# MCISO-S05-V00-CANIsolation.net
KiCad netlist of a schematic drawn in Altium Designer
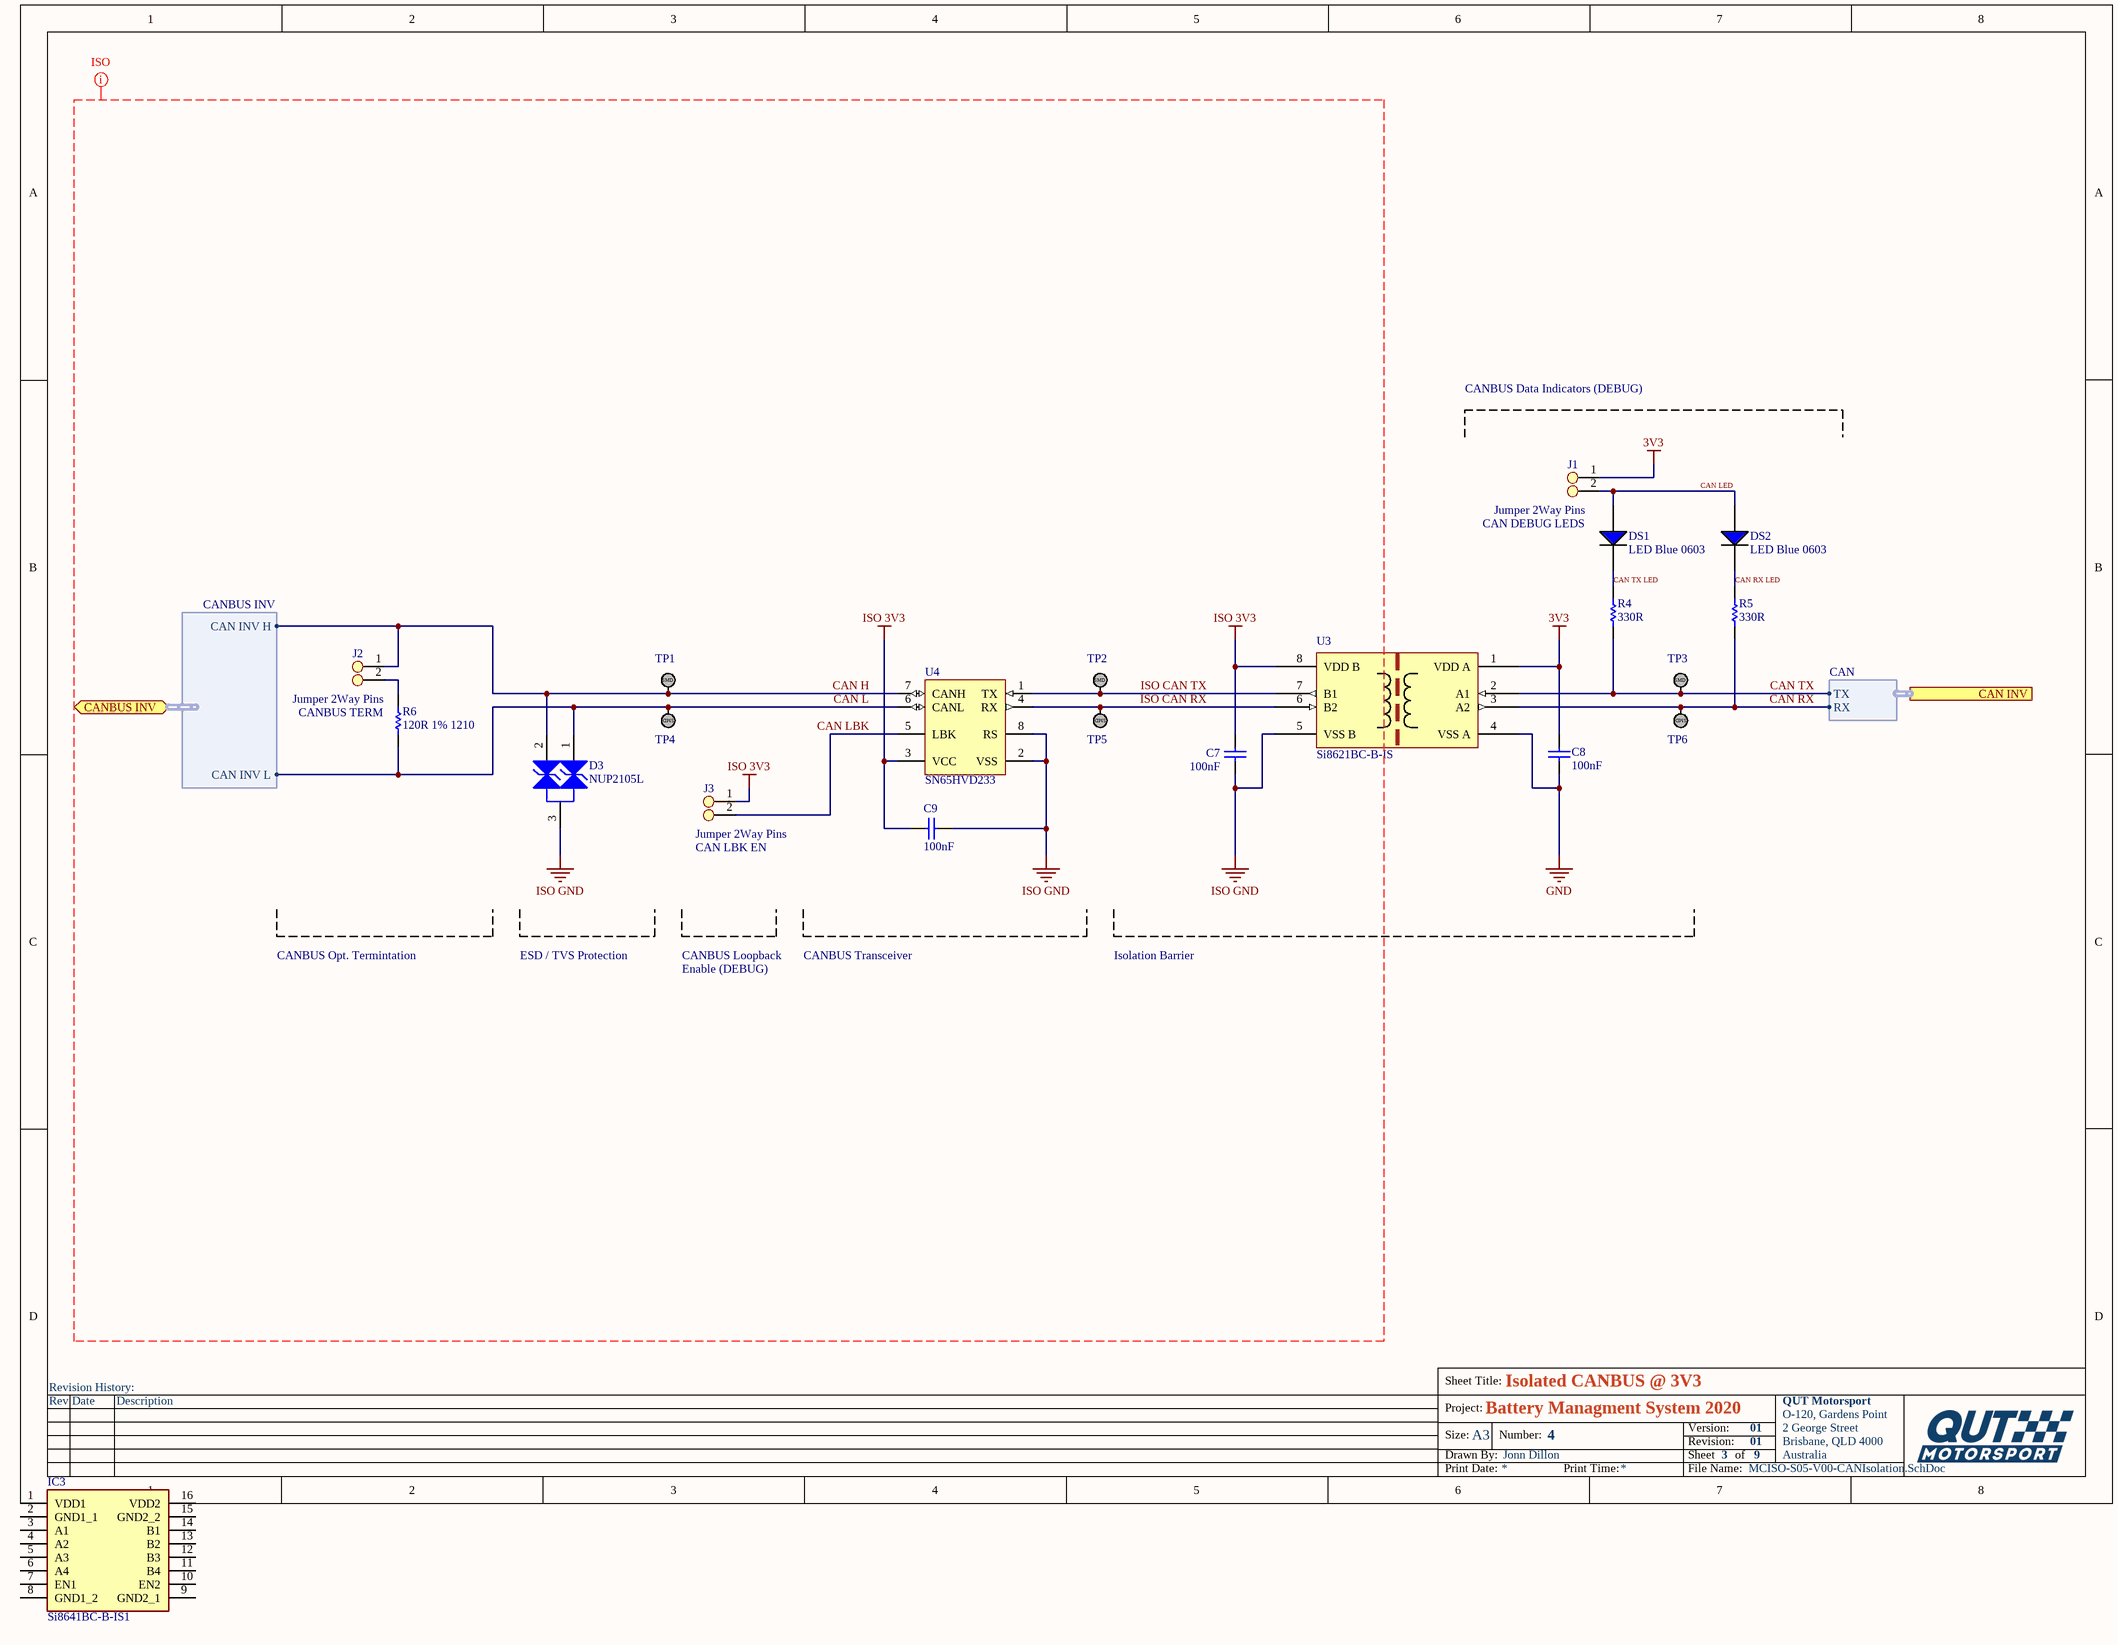
[diagram p0: MCISO-S05-V00-CANIsolation.SchDoc]

(export (version "E")
  (design (tool "Eeschema 10.0.6"))
  (components
    (comp (ref "C7")
      (value "100nF")
      (footprint "Cap_Ceramic_0603")
      (description "Capacitor, Ceramic, SMD, 100nF, 50V, 5%, X7R, 0603")
      (libsource (lib "StandardCapacitors") (part "100nF 50V 5% X7R 0603"))
    )
    (comp (ref "C8")
      (value "100nF")
      (footprint "Cap_Ceramic_0603")
      (description "Capacitor, Ceramic, SMD, 100nF, 50V, 5%, X7R, 0603")
      (libsource (lib "StandardCapacitors") (part "100nF 50V 5% X7R 0603"))
    )
    (comp (ref "C9")
      (value "100nF")
      (footprint "Cap_Ceramic_0603")
      (description "Capacitor, Ceramic, SMD, 100nF, 50V, 5%, X7R, 0603")
      (libsource (lib "StandardCapacitors") (part "100nF 50V 5% X7R 0603"))
    )
    (comp (ref "D3")
      (value "NUP2105L")
      (footprint "NUP2105L")
      (libsource (lib "QUTMS_CANLibrary") (part "NUP2105L"))
    )
    (comp (ref "DS1")
      (value "LED Blue 0603")
      (footprint "LED BLUE 0603")
      (libsource (lib "QUTMS_LEDLibrary") (part "LED BLUE 0603"))
    )
    (comp (ref "DS2")
      (value "LED Blue 0603")
      (footprint "LED BLUE 0603")
      (libsource (lib "QUTMS_LEDLibrary") (part "LED BLUE 0603"))
    )
    (comp (ref "IC3")
      (value "Si8641BC-B-IS1")
      (footprint "SamacSys:SOIC127P600X175-16N")
      (description "Integrated Circuit")
      (fields
        (field (name "MOUSER PART NUMBER") "634-SI8641BC-B-IS1")
        (field (name "ARROW PART NUMBER") "SI8641BC-B-IS1")
      )
      (libsource (lib "*") (part "Si8641BC-B-IS1"))
    )
    (comp (ref "J1")
      (value "Jumper 2Way Pins")
      (footprint "Jumper_2Way_Pin")
      (description "Jumper 2Way Side Pins")
      (libsource (lib "QUTMS_JumperLibrary") (part "Jumper 2Way Side Pins"))
    )
    (comp (ref "J2")
      (value "Jumper 2Way Pins")
      (footprint "Jumper_2Way_Pin")
      (description "Jumper 2Way Side Pins")
      (libsource (lib "QUTMS_JumperLibrary") (part "Jumper 2Way Side Pins"))
    )
    (comp (ref "J3")
      (value "Jumper 2Way Pins")
      (footprint "Jumper_2Way_Pin")
      (description "Jumper 2Way Side Pins")
      (libsource (lib "QUTMS_JumperLibrary") (part "Jumper 2Way Side Pins"))
    )
    (comp (ref "R4")
      (value "330R")
      (footprint "Res_ThinFilm_0603")
      (description "Resistor, SMD, 330R, 0.1W, 5%, 0603")
      (libsource (lib "StandardResistors") (part "330R 5% 0603"))
    )
    (comp (ref "R5")
      (value "330R")
      (footprint "Res_ThinFilm_0603")
      (description "Resistor, SMD, 330R, 0.1W, 5%, 0603")
      (libsource (lib "StandardResistors") (part "330R 5% 0603"))
    )
    (comp (ref "R6")
      (value "120R 1% 1210")
      (footprint "Res_ThinFilm_1210")
      (description "Resistor, SMD, 120R, 0.25W, 1%, 1210")
      (libsource (lib "StandardResistors") (part "120R 1% 1210"))
    )
    (comp (ref "TP1")
      (value "TestPoint_SMD")
      (footprint "TestPointSMD")
      (libsource (lib "StandardTest") (part "TestPoint_SMD"))
    )
    (comp (ref "TP2")
      (value "TestPoint_SMD")
      (footprint "TestPointSMD")
      (libsource (lib "StandardTest") (part "TestPoint_SMD"))
    )
    (comp (ref "TP3")
      (value "TestPoint_SMD")
      (footprint "TestPointSMD")
      (libsource (lib "StandardTest") (part "TestPoint_SMD"))
    )
    (comp (ref "TP4")
      (value "TestPoint_SMD")
      (footprint "TestPointSMD")
      (libsource (lib "StandardTest") (part "TestPoint_SMD"))
    )
    (comp (ref "TP5")
      (value "TestPoint_SMD")
      (footprint "TestPointSMD")
      (libsource (lib "StandardTest") (part "TestPoint_SMD"))
    )
    (comp (ref "TP6")
      (value "TestPoint_SMD")
      (footprint "TestPointSMD")
      (libsource (lib "StandardTest") (part "TestPoint_SMD"))
    )
    (comp (ref "U3")
      (value "Si8621BC-B-IS")
      (footprint "Si8621BC-B-IS")
      (libsource (lib "QUTMS_IsolatorLibrary") (part "Si8621BC-B-IS"))
    )
    (comp (ref "U4")
      (value "SN65HVD233")
      (footprint "SN65HVD233DR")
      (libsource (lib "QUTMS_CANLibrary") (part "SN65HVD233"))
    )
  )
  (nets
    (net (code "4") (name "/CAN H") (class "Default")
      (node (ref "D3") (pin "2") (pinfunction "2_2") (pintype "passive"))
      (node (ref "J2") (pin "1") (pinfunction "1_1") (pintype "passive"))
      (node (ref "TP1") (pin "1") (pinfunction "1_1") (pintype "passive"))
      (node (ref "U4") (pin "7") (pinfunction "CANH_7") (pintype "bidirectional"))
    )
    (net (code "5") (name "/CAN L") (class "Default")
      (node (ref "D3") (pin "1") (pinfunction "1_1") (pintype "passive"))
      (node (ref "R6") (pin "1") (pinfunction "1_1") (pintype "passive"))
      (node (ref "TP4") (pin "1") (pinfunction "1_1") (pintype "passive"))
      (node (ref "U4") (pin "6") (pinfunction "CANL_6") (pintype "bidirectional"))
    )
    (net (code "6") (name "/CAN LBK") (class "Default")
      (node (ref "J3") (pin "2") (pinfunction "2_2") (pintype "passive"))
      (node (ref "U4") (pin "5") (pinfunction "LBK_5") (pintype "passive"))
    )
    (net (code "7") (name "/CAN LED") (class "Default")
      (node (ref "DS1") (pin "1") (pinfunction "A_1") (pintype "passive"))
      (node (ref "DS2") (pin "1") (pinfunction "A_1") (pintype "passive"))
      (node (ref "J1") (pin "2") (pinfunction "2_2") (pintype "passive"))
    )
    (net (code "8") (name "/CAN RX") (class "Default")
      (node (ref "R5") (pin "1") (pinfunction "1_1") (pintype "passive"))
      (node (ref "TP6") (pin "1") (pinfunction "1_1") (pintype "passive"))
      (node (ref "U3") (pin "3") (pinfunction "A2_3") (pintype "output"))
    )
    (net (code "9") (name "/CAN RX LED") (class "Default")
      (node (ref "DS2") (pin "2") (pinfunction "C_2") (pintype "passive"))
      (node (ref "R5") (pin "2") (pinfunction "2_2") (pintype "passive"))
    )
    (net (code "10") (name "/CAN TX") (class "Default")
      (node (ref "R4") (pin "1") (pinfunction "1_1") (pintype "passive"))
      (node (ref "TP3") (pin "1") (pinfunction "1_1") (pintype "passive"))
      (node (ref "U3") (pin "2") (pinfunction "A1_2") (pintype "input"))
    )
    (net (code "11") (name "/CAN TX LED") (class "Default")
      (node (ref "DS1") (pin "2") (pinfunction "C_2") (pintype "passive"))
      (node (ref "R4") (pin "2") (pinfunction "2_2") (pintype "passive"))
    )
    (net (code "12") (name "/ISO CAN RX") (class "Default")
      (node (ref "TP5") (pin "1") (pinfunction "1_1") (pintype "passive"))
      (node (ref "U3") (pin "6") (pinfunction "B2_6") (pintype "input"))
      (node (ref "U4") (pin "4") (pinfunction "RX_4") (pintype "output"))
    )
    (net (code "13") (name "/ISO CAN TX") (class "Default")
      (node (ref "TP2") (pin "1") (pinfunction "1_1") (pintype "passive"))
      (node (ref "U3") (pin "7") (pinfunction "B1_7") (pintype "output"))
      (node (ref "U4") (pin "1") (pinfunction "TX_1") (pintype "input"))
    )
    (net (code "16") (name "3V3") (class "Default")
      (node (ref "C8") (pin "2") (pinfunction "2_2") (pintype "passive"))
      (node (ref "J1") (pin "1") (pinfunction "1_1") (pintype "passive"))
      (node (ref "U3") (pin "1") (pinfunction "VDD_A_1") (pintype "passive"))
    )
    (net (code "17") (name "GND") (class "Default")
      (node (ref "C8") (pin "1") (pinfunction "1_1") (pintype "passive"))
      (node (ref "U3") (pin "4") (pinfunction "VSS_A_4") (pintype "passive"))
    )
    (net (code "18") (name "ISO 3V3") (class "Default")
      (node (ref "C7") (pin "2") (pinfunction "2_2") (pintype "passive"))
      (node (ref "C9") (pin "2") (pinfunction "2_2") (pintype "passive"))
      (node (ref "J3") (pin "1") (pinfunction "1_1") (pintype "passive"))
      (node (ref "U3") (pin "8") (pinfunction "VDD_B_8") (pintype "passive"))
      (node (ref "U4") (pin "3") (pinfunction "VCC_3") (pintype "passive"))
    )
    (net (code "19") (name "ISO GND") (class "Default")
      (node (ref "C7") (pin "1") (pinfunction "1_1") (pintype "passive"))
      (node (ref "C9") (pin "1") (pinfunction "1_1") (pintype "passive"))
      (node (ref "D3") (pin "3") (pinfunction "3_3") (pintype "passive"))
      (node (ref "U3") (pin "5") (pinfunction "VSS_B_5") (pintype "passive"))
      (node (ref "U4") (pin "2") (pinfunction "VSS_2") (pintype "passive"))
      (node (ref "U4") (pin "8") (pinfunction "RS_8") (pintype "passive"))
    )
    (net (code "20") (name "Net-(J2-Pad2)") (class "Default")
      (node (ref "J2") (pin "2") (pinfunction "2_2") (pintype "passive"))
      (node (ref "R6") (pin "2") (pinfunction "2_2") (pintype "passive"))
    )
    (net (code "21") (name "unconnected-(IC3-A1-Pad3)") (class "Default")
      (node (ref "IC3") (pin "3") (pinfunction "A1_3") (pintype "passive"))
    )
    (net (code "22") (name "unconnected-(IC3-A2-Pad4)") (class "Default")
      (node (ref "IC3") (pin "4") (pinfunction "A2_4") (pintype "passive"))
    )
    (net (code "23") (name "unconnected-(IC3-A3-Pad5)") (class "Default")
      (node (ref "IC3") (pin "5") (pinfunction "A3_5") (pintype "passive"))
    )
    (net (code "24") (name "unconnected-(IC3-A4-Pad6)") (class "Default")
      (node (ref "IC3") (pin "6") (pinfunction "A4_6") (pintype "passive"))
    )
    (net (code "25") (name "unconnected-(IC3-B1-Pad14)") (class "Default")
      (node (ref "IC3") (pin "14") (pinfunction "B1_14") (pintype "passive"))
    )
    (net (code "26") (name "unconnected-(IC3-B2-Pad13)") (class "Default")
      (node (ref "IC3") (pin "13") (pinfunction "B2_13") (pintype "passive"))
    )
    (net (code "27") (name "unconnected-(IC3-B3-Pad12)") (class "Default")
      (node (ref "IC3") (pin "12") (pinfunction "B3_12") (pintype "passive"))
    )
    (net (code "28") (name "unconnected-(IC3-B4-Pad11)") (class "Default")
      (node (ref "IC3") (pin "11") (pinfunction "B4_11") (pintype "passive"))
    )
    (net (code "29") (name "unconnected-(IC3-EN1-Pad7)") (class "Default")
      (node (ref "IC3") (pin "7") (pinfunction "EN1_7") (pintype "passive"))
    )
    (net (code "30") (name "unconnected-(IC3-EN2-Pad10)") (class "Default")
      (node (ref "IC3") (pin "10") (pinfunction "EN2_10") (pintype "passive"))
    )
    (net (code "31") (name "unconnected-(IC3-GND1_1-Pad2)") (class "Default")
      (node (ref "IC3") (pin "2") (pinfunction "GND1_1_2") (pintype "passive"))
    )
    (net (code "32") (name "unconnected-(IC3-GND1_2-Pad8)") (class "Default")
      (node (ref "IC3") (pin "8") (pinfunction "GND1_2_8") (pintype "passive"))
    )
    (net (code "33") (name "unconnected-(IC3-GND2_1-Pad9)") (class "Default")
      (node (ref "IC3") (pin "9") (pinfunction "GND2_1_9") (pintype "passive"))
    )
    (net (code "34") (name "unconnected-(IC3-GND2_2-Pad15)") (class "Default")
      (node (ref "IC3") (pin "15") (pinfunction "GND2_2_15") (pintype "passive"))
    )
    (net (code "35") (name "unconnected-(IC3-VDD1-Pad1)") (class "Default")
      (node (ref "IC3") (pin "1") (pinfunction "VDD1_1") (pintype "passive"))
    )
    (net (code "36") (name "unconnected-(IC3-VDD2-Pad16)") (class "Default")
      (node (ref "IC3") (pin "16") (pinfunction "VDD2_16") (pintype "passive"))
    )
  )
)
